# main.net
KiCad netlist of a schematic drawn in EAGLE
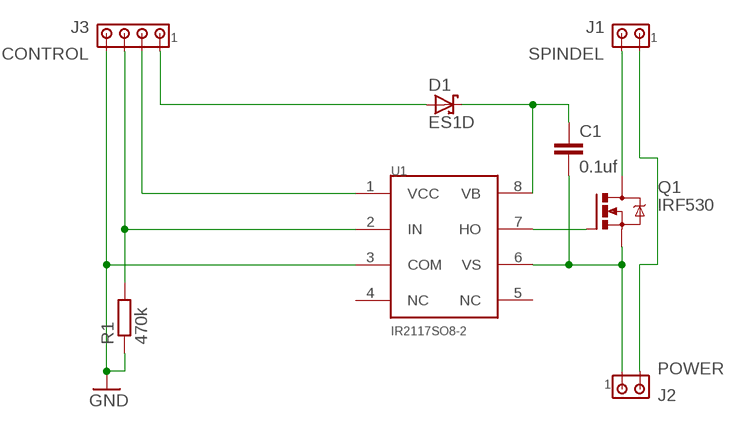
[diagram p0: schematic, sheet 1]

(export (version "E")
  (design (tool "Eeschema 10.0.6"))
  (components
    (comp (ref "C1")
      (value "0.1uf")
      (footprint "eagle-import:C0805K")
      (libsource (lib "eagle-import") (part "C-EUC0805K"))
    )
    (comp (ref "D1")
      (value "ES1D")
      (footprint "eagle-import:SMB")
      (libsource (lib "eagle-import") (part "SCHOTTKY-DIODESMD"))
    )
    (comp (ref "J1")
      (value "SPINDEL")
      (footprint "eagle-import:10X02MTA")
      (libsource (lib "eagle-import") (part "MTA02-100"))
    )
    (comp (ref "J2")
      (value "POWER")
      (footprint "eagle-import:10X02MTA")
      (libsource (lib "eagle-import") (part "MTA02-100"))
    )
    (comp (ref "J3")
      (value "CONTROL")
      (footprint "eagle-import:10X04MTA")
      (libsource (lib "eagle-import") (part "MTA04-100"))
    )
    (comp (ref "Q1")
      (value "IRF530")
      (footprint "eagle-import:TO220BV")
      (libsource (lib "eagle-import") (part "IRF530"))
    )
    (comp (ref "R1")
      (value "470k")
      (footprint "eagle-import:R0603")
      (libsource (lib "eagle-import") (part "R-EU_R0603"))
    )
    (comp (ref "U1")
      (value "IR2117SO8-2")
      (footprint "eagle-import:SO8-2")
      (libsource (lib "eagle-import") (part "IR2117SO8-2"))
    )
  )
  (nets
    (net (code "1") (name "GND") (class "Default")
      (node (ref "J3") (pin "4") (pinfunction "4_4") (pintype "passive"))
      (node (ref "R1") (pin "1") (pinfunction "1_1") (pintype "passive"))
      (node (ref "U1") (pin "3") (pinfunction "COM_3") (pintype "power_in"))
    )
    (net (code "2") (name "Net-(D1-PadA)") (class "Default")
      (node (ref "D1") (pin "A") (pinfunction "A_A") (pintype "passive"))
      (node (ref "J3") (pin "1") (pinfunction "1_1") (pintype "passive"))
    )
    (net (code "3") (name "Net-(J1-Pad1)") (class "Default")
      (node (ref "J1") (pin "1") (pinfunction "1_1") (pintype "passive"))
      (node (ref "J2") (pin "2") (pinfunction "2_2") (pintype "passive"))
    )
    (net (code "4") (name "Net-(J1-Pad2)") (class "Default")
      (node (ref "J1") (pin "2") (pinfunction "2_2") (pintype "passive"))
      (node (ref "Q1") (pin "D") (pinfunction "D_D") (pintype "passive"))
    )
    (net (code "5") (name "Net-(U1-HO)") (class "Default")
      (node (ref "Q1") (pin "G") (pinfunction "G_G") (pintype "passive"))
      (node (ref "U1") (pin "7") (pinfunction "HO_7") (pintype "output"))
    )
    (net (code "6") (name "Net-(U1-IN)") (class "Default")
      (node (ref "J3") (pin "3") (pinfunction "3_3") (pintype "passive"))
      (node (ref "R1") (pin "2") (pinfunction "2_2") (pintype "passive"))
      (node (ref "U1") (pin "2") (pinfunction "IN_2") (pintype "input"))
    )
    (net (code "7") (name "Net-(U1-VB)") (class "Default")
      (node (ref "C1") (pin "1") (pinfunction "1_1") (pintype "passive"))
      (node (ref "D1") (pin "C") (pinfunction "C_C") (pintype "passive"))
      (node (ref "U1") (pin "8") (pinfunction "VB_8") (pintype "power_in"))
    )
    (net (code "8") (name "Net-(U1-VCC)") (class "Default")
      (node (ref "J3") (pin "2") (pinfunction "2_2") (pintype "passive"))
      (node (ref "U1") (pin "1") (pinfunction "VCC_1") (pintype "power_in"))
    )
    (net (code "9") (name "Net-(U1-VS)") (class "Default")
      (node (ref "C1") (pin "2") (pinfunction "2_2") (pintype "passive"))
      (node (ref "J2") (pin "1") (pinfunction "1_1") (pintype "passive"))
      (node (ref "Q1") (pin "S") (pinfunction "S_S") (pintype "passive"))
      (node (ref "U1") (pin "6") (pinfunction "VS_6") (pintype "power_in"))
    )
    (net (code "10") (name "unconnected-(U1-NC-Pad4)") (class "Default")
      (node (ref "U1") (pin "4") (pinfunction "NC_4") (pintype "no_connect"))
    )
    (net (code "11") (name "unconnected-(U1-NC-Pad5)") (class "Default")
      (node (ref "U1") (pin "5") (pinfunction "NC_5") (pintype "no_connect"))
    )
  )
)
